# Half_Bridge_Driver.net
KiCad netlist of a schematic drawn in Altium Designer
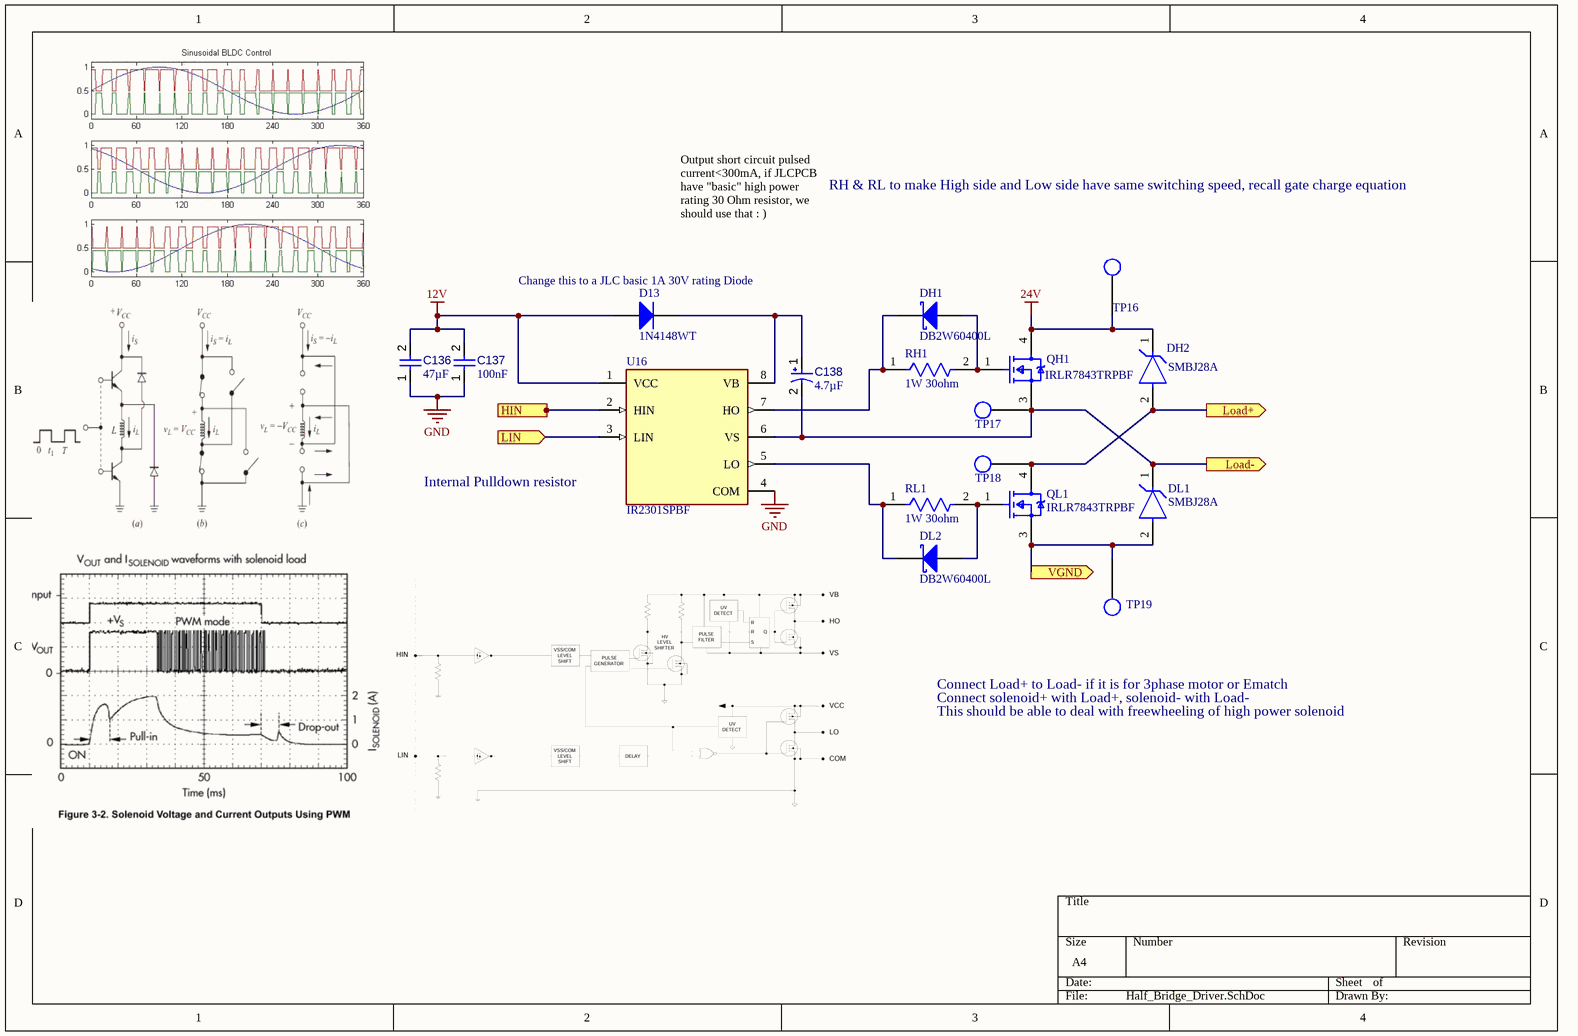
[diagram p0: Half_Bridge_Driver.SchDoc]

(export (version "E")
  (design (tool "Eeschema 10.0.6"))
  (components
    (comp (ref "C136")
      (value "47µF")
      (footprint "CAPC0805(2012)145_L")
      (description "Chip Capacitor, 47µF +/-40%, 6.3V, 0805, Thickness 1.45 mm")
      (fields (field (name "TOLERANCE") "10%") (field (name "Comment") "Capacitor 47µF +/-40% 6.3V 0805"))
      (libsource (lib "Yuxuan chen") (part "CAP-NP-2"))
    )
    (comp (ref "C137")
      (value "100nF")
      (footprint "CAPC2013X95X50LL10T25")
      (description "Chip Capacitor, 100 nF, +/- 10%, 50 V, 0805 (2012 Metric)")
      (fields (field (name "TOLERANCE") "10%") (field (name "Comment") "Capacitor 100 nF +/-10% 50 V 0805"))
      (libsource (lib "Yuxuan chen") (part "CAP-NP-2"))
    )
    (comp (ref "C138")
      (value "4.7µF")
      (footprint "CAPPR55-200-1100X500X1200")
      (description "Aluminum Electrolytic Capacitor, 4.7 uF, +/- 20%, 50 V, -40 to 85 degC, 2-Pin THD, RoHS, Bulk")
      (fields (field (name "MANUFACTURER") "Panasonic") (field (name "TOLERANCE") "20%"))
      (libsource (lib "Yuxuan chen") (part "CAP-P-2"))
    )
    (comp (ref "D13")
      (value "1N4148WT")
      (footprint "FAIR-SOD-523F-2_V")
      (description "High Conductance Fast Switching Diode, 75 V, -55 to 150 degC, 2-Pin SOD523F, RoHS")
      (fields (field (name "MANUFACTURER") "Fairchild Semiconductor"))
      (libsource (lib "Altium Content Vault") (part "FAIR-D_K1A2-2"))
    )
    (comp (ref "DH1")
      (value "DB2W60400L")
      (footprint "PNSC-Mini2-F3-B-2_V")
      (fields (field (name "MANUFACTURER") "Panasonic"))
      (libsource (lib "Altium Content Vault") (part "DSKY-AK-2"))
    )
    (comp (ref "DH2")
      (value "SMBJ28A")
      (footprint "FP-SMBJ-MFG")
      (description "TVS DIODE 28V 45.4V DO214AA")
      (fields
        (field (name "MANUFACTURER") "Littelfuse Inc")
        (field (name "OCTOPART") "https://octopart.com/smbj28a-littelfuse-350790")
      )
      (libsource (lib "Altium Content Vault") (part "f813f71cba58e380607f5dd3caf9714"))
    )
    (comp (ref "DL1")
      (value "SMBJ28A")
      (footprint "FP-SMBJ-MFG")
      (description "TVS DIODE 28V 45.4V DO214AA")
      (fields
        (field (name "MANUFACTURER") "Littelfuse Inc")
        (field (name "OCTOPART") "https://octopart.com/smbj28a-littelfuse-350790")
      )
      (libsource (lib "Altium Content Vault") (part "f813f71cba58e380607f5dd3caf9714"))
    )
    (comp (ref "DL2")
      (value "DB2W60400L")
      (footprint "PNSC-Mini2-F3-B-2_V")
      (fields (field (name "MANUFACTURER") "Panasonic"))
      (libsource (lib "Altium Content Vault") (part "DSKY-AK-2"))
    )
    (comp (ref "QH1")
      (value "IRLR7843TRPBF")
      (footprint "FP-PG-TO252-3-MFG")
      (description "MOSFET N-CH 30V 161A DPAK")
      (fields
        (field (name "OCTOPART") "https://octopart.com/irlr7843trpbf-infineon-65875062")
        (field (name "MANUFACTURER") "Infineon")
      )
      (libsource (lib "Altium Content Vault") (part "2f21c11e83d30f418bb422e5a3b3d11"))
    )
    (comp (ref "QL1")
      (value "IRLR7843TRPBF")
      (footprint "FP-PG-TO252-3-MFG")
      (description "MOSFET N-CH 30V 161A DPAK")
      (fields
        (field (name "OCTOPART") "https://octopart.com/irlr7843trpbf-infineon-65875062")
        (field (name "MANUFACTURER") "Infineon")
      )
      (libsource (lib "Altium Content Vault") (part "2f21c11e83d30f418bb422e5a3b3d11"))
    )
    (comp (ref "RH1")
      (value "1W 30ohm")
      (footprint "FP-RMCF2512-IPC_C")
      (description "30Ω ±5% 1W 2512 Thick Film Chip Resistor AEC-Q200 compliant")
      (fields (field (name "TOLERANCE") "5%"))
      (libsource (lib "Altium Content Vault") (part "1029c3af85768c4190bb7ad29bc67b5"))
    )
    (comp (ref "RL1")
      (value "1W 30ohm")
      (footprint "FP-RMCF2512-IPC_C")
      (description "30Ω ±5% 1W 2512 Thick Film Chip Resistor AEC-Q200 compliant")
      (fields (field (name "TOLERANCE") "5%"))
      (libsource (lib "Altium Content Vault") (part "1029c3af85768c4190bb7ad29bc67b5"))
    )
    (comp (ref "TP16")
      (value "BURPG_TestPoint1")
      (footprint "BURPG_TestPoint1")
      (libsource (lib "BURPG_generic") (part "BURPG_TestPoint1"))
    )
    (comp (ref "TP17")
      (value "BURPG_TestPoint1")
      (footprint "BURPG_TestPoint1")
      (libsource (lib "BURPG_generic") (part "BURPG_TestPoint1"))
    )
    (comp (ref "TP18")
      (value "BURPG_TestPoint1")
      (footprint "BURPG_TestPoint1")
      (libsource (lib "BURPG_generic") (part "BURPG_TestPoint1"))
    )
    (comp (ref "TP19")
      (value "BURPG_TestPoint1")
      (footprint "BURPG_TestPoint1")
      (libsource (lib "BURPG_generic") (part "BURPG_TestPoint1"))
    )
    (comp (ref "U16")
      (value "IR2301SPBF")
      (footprint "FP-PG-DSO-8-IPC_C")
      (description "IC GATE DRVR HI/LOW SIDE 8SOIC")
      (libsource (lib "Altium Content Vault") (part "2b90cc40879ec235d499f012fb868c8"))
    )
  )
  (nets
    (net (code "1") (name "/HIN") (class "Default")
      (node (ref "U16") (pin "2") (pinfunction "HIN_2") (pintype "input"))
    )
    (net (code "2") (name "/LIN") (class "Default")
      (node (ref "U16") (pin "3") (pinfunction "LIN_3") (pintype "input"))
    )
    (net (code "3") (name "/Load+") (class "Default")
      (node (ref "DH2") (pin "2") (pinfunction "A_2") (pintype "passive"))
      (node (ref "QL1") (pin "4") (pinfunction "DRAIN_4") (pintype "passive"))
      (node (ref "TP18") (pin "1") (pinfunction "1_1") (pintype "passive"))
    )
    (net (code "4") (name "/Load-") (class "Default")
      (node (ref "C138") (pin "2") (pinfunction "2_2") (pintype "passive"))
      (node (ref "DL1") (pin "1") (pinfunction "C_1") (pintype "passive"))
      (node (ref "QH1") (pin "3") (pinfunction "SOURCE_3") (pintype "passive"))
      (node (ref "TP17") (pin "1") (pinfunction "1_1") (pintype "passive"))
      (node (ref "U16") (pin "6") (pinfunction "VS_6") (pintype "power_in"))
    )
    (net (code "5") (name "/VGND") (class "Default")
      (node (ref "DL1") (pin "2") (pinfunction "A_2") (pintype "passive"))
      (node (ref "QL1") (pin "3") (pinfunction "SOURCE_3") (pintype "passive"))
      (node (ref "TP19") (pin "1") (pinfunction "1_1") (pintype "passive"))
    )
    (net (code "6") (name "12V") (class "Default")
      (node (ref "C136") (pin "2") (pinfunction "2_2") (pintype "passive"))
      (node (ref "C137") (pin "2") (pinfunction "2_2") (pintype "passive"))
      (node (ref "D13") (pin "2") (pinfunction "A_2") (pintype "passive"))
      (node (ref "U16") (pin "1") (pinfunction "VCC_1") (pintype "power_in"))
    )
    (net (code "7") (name "24V") (class "Default")
      (node (ref "DH2") (pin "1") (pinfunction "C_1") (pintype "passive"))
      (node (ref "QH1") (pin "4") (pinfunction "DRAIN_4") (pintype "passive"))
      (node (ref "TP16") (pin "1") (pinfunction "1_1") (pintype "passive"))
    )
    (net (code "8") (name "GND") (class "Default")
      (node (ref "C136") (pin "1") (pinfunction "1_1") (pintype "passive"))
      (node (ref "C137") (pin "1") (pinfunction "1_1") (pintype "passive"))
      (node (ref "U16") (pin "4") (pinfunction "COM_4") (pintype "passive"))
    )
    (net (code "9") (name "Net-(D13-K)") (class "Default")
      (node (ref "C138") (pin "1") (pinfunction "1_1") (pintype "passive"))
      (node (ref "D13") (pin "1") (pinfunction "K_1") (pintype "passive"))
      (node (ref "U16") (pin "8") (pinfunction "VB_8") (pintype "power_in"))
    )
    (net (code "10") (name "Net-(DH1-A)") (class "Default")
      (node (ref "DH1") (pin "1") (pinfunction "A_1") (pintype "passive"))
      (node (ref "QH1") (pin "1") (pinfunction "GATE_1") (pintype "passive"))
      (node (ref "RH1") (pin "2") (pinfunction "2_2") (pintype "passive"))
    )
    (net (code "11") (name "Net-(DH1-K)") (class "Default")
      (node (ref "DH1") (pin "2") (pinfunction "K_2") (pintype "passive"))
      (node (ref "RH1") (pin "1") (pinfunction "1_1") (pintype "passive"))
      (node (ref "U16") (pin "7") (pinfunction "HO_7") (pintype "output"))
    )
    (net (code "12") (name "Net-(DL2-A)") (class "Default")
      (node (ref "DL2") (pin "1") (pinfunction "A_1") (pintype "passive"))
      (node (ref "QL1") (pin "1") (pinfunction "GATE_1") (pintype "passive"))
      (node (ref "RL1") (pin "2") (pinfunction "2_2") (pintype "passive"))
    )
    (net (code "13") (name "Net-(DL2-K)") (class "Default")
      (node (ref "DL2") (pin "2") (pinfunction "K_2") (pintype "passive"))
      (node (ref "RL1") (pin "1") (pinfunction "1_1") (pintype "passive"))
      (node (ref "U16") (pin "5") (pinfunction "LO_5") (pintype "output"))
    )
  )
)
